# Sony_keyboard.net
KiCad netlist of a schematic drawn in EAGLE
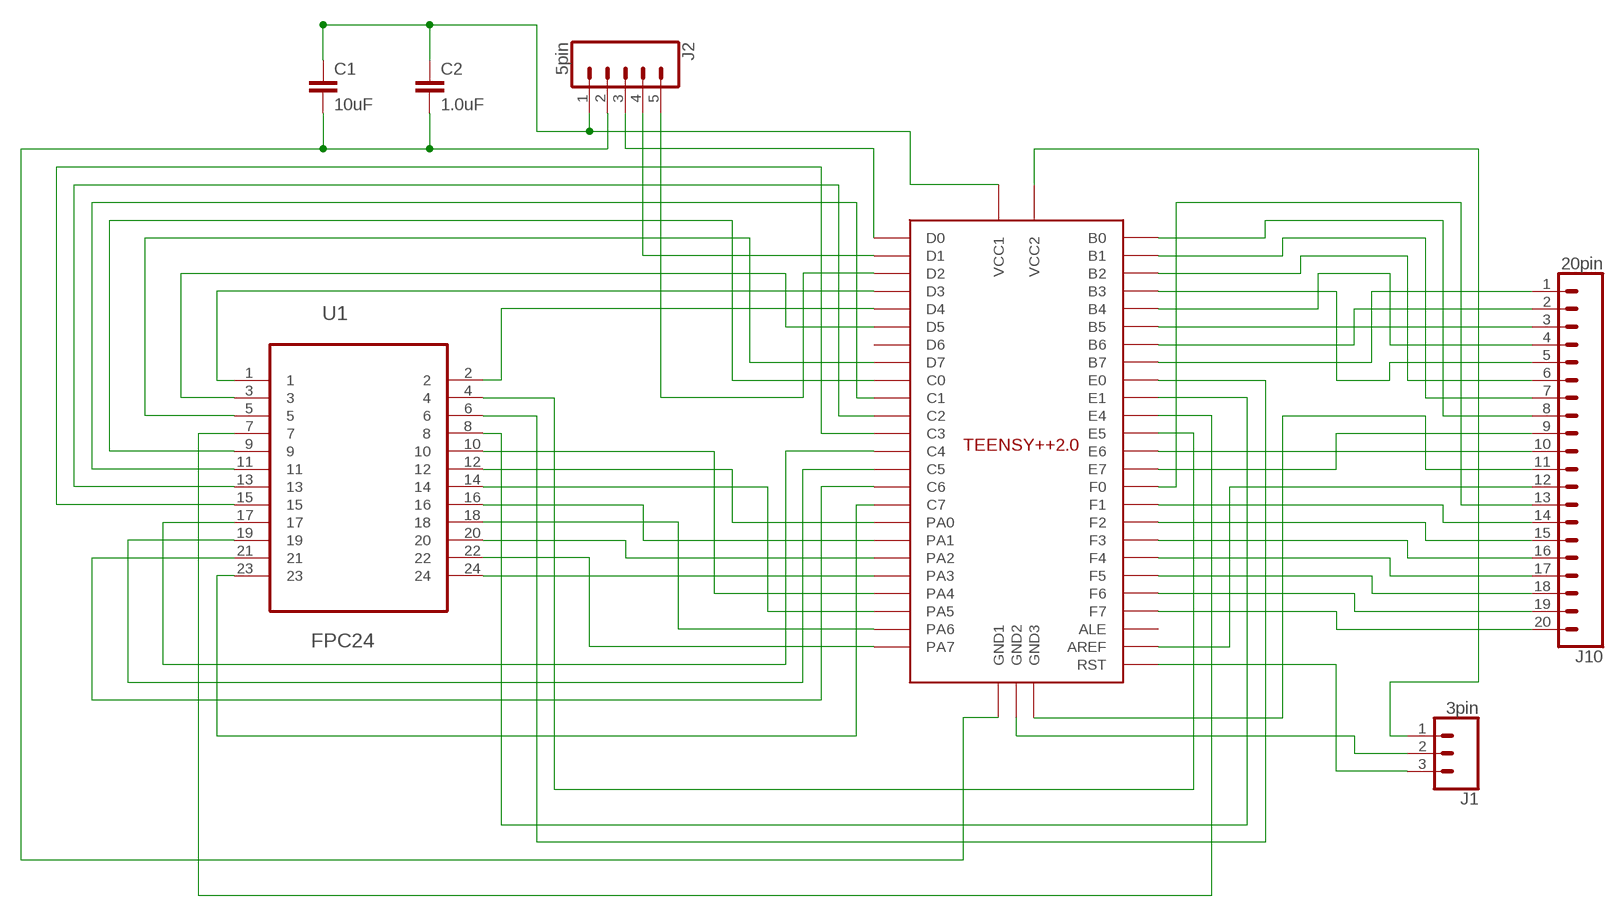
[diagram p0: schematic, sheet 1]

(export (version "E")
  (design (tool "Eeschema 10.0.6"))
  (components
    (comp (ref "C1")
      (value "10uF")
      (footprint "eagle-import:0603")
      (libsource (lib "eagle-import") (part "10UF-0603-6.3V-20%"))
    )
    (comp (ref "C2")
      (value "1.0uF")
      (footprint "eagle-import:0603")
      (libsource (lib "eagle-import") (part "1.0UF-0603-16V-10%"))
    )
    (comp (ref "J1")
      (value "3pin")
      (footprint "eagle-import:1X03")
      (libsource (lib "eagle-import") (part "CONN_03"))
    )
    (comp (ref "J2")
      (value "5pin")
      (footprint "eagle-import:1X05")
      (libsource (lib "eagle-import") (part "CONN_05"))
    )
    (comp (ref "J10")
      (value "20pin")
      (footprint "eagle-import:1X20")
      (libsource (lib "eagle-import") (part "CONN_20"))
    )
    (comp (ref "U1")
      (value "FPC24")
      (footprint "eagle-import:FPC24")
      (libsource (lib "eagle-import") (part "FPC24"))
    )
    (comp (ref "U2")
      (value "Teensy++2.0")
      (footprint "eagle-import:TEENSYPP2.0")
      (libsource (lib "eagle-import") (part "TEENSYPP2.0"))
    )
  )
  (nets
    (net (code "1") (name "Net-(C1-Pad1)") (class "Default")
      (node (ref "C1") (pin "1") (pinfunction "1_1") (pintype "passive"))
      (node (ref "C2") (pin "1") (pinfunction "1_1") (pintype "passive"))
      (node (ref "J2") (pin "1") (pinfunction "1_1") (pintype "passive"))
      (node (ref "U2") (pin "VCC1") (pinfunction "VCC1_VCC1") (pintype "bidirectional"))
    )
    (net (code "2") (name "Net-(C1-Pad2)") (class "Default")
      (node (ref "C1") (pin "2") (pinfunction "2_2") (pintype "passive"))
      (node (ref "C2") (pin "2") (pinfunction "2_2") (pintype "passive"))
      (node (ref "J2") (pin "2") (pinfunction "2_2") (pintype "passive"))
      (node (ref "U2") (pin "GND1") (pinfunction "GND1_GND1") (pintype "bidirectional"))
    )
    (net (code "3") (name "Net-(J1-Pad1)") (class "Default")
      (node (ref "J1") (pin "1") (pinfunction "1_1") (pintype "passive"))
      (node (ref "U2") (pin "VCC2") (pinfunction "VCC2_VCC2") (pintype "bidirectional"))
    )
    (net (code "4") (name "Net-(J1-Pad2)") (class "Default")
      (node (ref "J1") (pin "2") (pinfunction "2_2") (pintype "passive"))
      (node (ref "U2") (pin "GND2") (pinfunction "GND2_GND2") (pintype "bidirectional"))
    )
    (net (code "5") (name "Net-(J1-Pad3)") (class "Default")
      (node (ref "J1") (pin "3") (pinfunction "3_3") (pintype "passive"))
      (node (ref "U2") (pin "RST") (pinfunction "RST_RST") (pintype "bidirectional"))
    )
    (net (code "6") (name "Net-(J2-Pad3)") (class "Default")
      (node (ref "J2") (pin "3") (pinfunction "3_3") (pintype "passive"))
      (node (ref "U2") (pin "D0") (pinfunction "D0_D0") (pintype "bidirectional"))
    )
    (net (code "7") (name "Net-(J2-Pad4)") (class "Default")
      (node (ref "J2") (pin "4") (pinfunction "4_4") (pintype "passive"))
      (node (ref "U2") (pin "D1") (pinfunction "D1_D1") (pintype "bidirectional"))
    )
    (net (code "8") (name "Net-(J2-Pad5)") (class "Default")
      (node (ref "J2") (pin "5") (pinfunction "5_5") (pintype "passive"))
      (node (ref "U2") (pin "D2") (pinfunction "D2_D2") (pintype "bidirectional"))
    )
    (net (code "9") (name "Net-(J10-Pad1)") (class "Default")
      (node (ref "J10") (pin "1") (pinfunction "1_1") (pintype "passive"))
      (node (ref "U2") (pin "B7") (pinfunction "B7_B7") (pintype "bidirectional"))
    )
    (net (code "10") (name "Net-(J10-Pad2)") (class "Default")
      (node (ref "J10") (pin "2") (pinfunction "2_2") (pintype "passive"))
      (node (ref "U2") (pin "B6") (pinfunction "B6_B6") (pintype "bidirectional"))
    )
    (net (code "11") (name "Net-(J10-Pad3)") (class "Default")
      (node (ref "J10") (pin "3") (pinfunction "3_3") (pintype "passive"))
      (node (ref "U2") (pin "B5") (pinfunction "B5_B5") (pintype "bidirectional"))
    )
    (net (code "12") (name "Net-(J10-Pad4)") (class "Default")
      (node (ref "J10") (pin "4") (pinfunction "4_4") (pintype "passive"))
      (node (ref "U2") (pin "B4") (pinfunction "B4_B4") (pintype "bidirectional"))
    )
    (net (code "13") (name "Net-(J10-Pad5)") (class "Default")
      (node (ref "J10") (pin "5") (pinfunction "5_5") (pintype "passive"))
      (node (ref "U2") (pin "B3") (pinfunction "B3_B3") (pintype "bidirectional"))
    )
    (net (code "14") (name "Net-(J10-Pad6)") (class "Default")
      (node (ref "J10") (pin "6") (pinfunction "6_6") (pintype "passive"))
      (node (ref "U2") (pin "B2") (pinfunction "B2_B2") (pintype "bidirectional"))
    )
    (net (code "15") (name "Net-(J10-Pad7)") (class "Default")
      (node (ref "J10") (pin "7") (pinfunction "7_7") (pintype "passive"))
      (node (ref "U2") (pin "B1") (pinfunction "B1_B1") (pintype "bidirectional"))
    )
    (net (code "16") (name "Net-(J10-Pad8)") (class "Default")
      (node (ref "J10") (pin "8") (pinfunction "8_8") (pintype "passive"))
      (node (ref "U2") (pin "B0") (pinfunction "B0_B0") (pintype "bidirectional"))
    )
    (net (code "17") (name "Net-(J10-Pad9)") (class "Default")
      (node (ref "J10") (pin "9") (pinfunction "9_9") (pintype "passive"))
      (node (ref "U2") (pin "E7") (pinfunction "E7_E7") (pintype "bidirectional"))
    )
    (net (code "18") (name "Net-(J10-Pad10)") (class "Default")
      (node (ref "J10") (pin "10") (pinfunction "10_10") (pintype "passive"))
      (node (ref "U2") (pin "E6") (pinfunction "E6_E6") (pintype "bidirectional"))
    )
    (net (code "19") (name "Net-(J10-Pad11)") (class "Default")
      (node (ref "J10") (pin "11") (pinfunction "11_11") (pintype "passive"))
      (node (ref "U2") (pin "GND3") (pinfunction "GND3_GND3") (pintype "bidirectional"))
    )
    (net (code "20") (name "Net-(J10-Pad12)") (class "Default")
      (node (ref "J10") (pin "12") (pinfunction "12_12") (pintype "passive"))
      (node (ref "U2") (pin "AREF") (pinfunction "AREF_AREF") (pintype "bidirectional"))
    )
    (net (code "21") (name "Net-(J10-Pad13)") (class "Default")
      (node (ref "J10") (pin "13") (pinfunction "13_13") (pintype "passive"))
      (node (ref "U2") (pin "F0") (pinfunction "F0_F0") (pintype "bidirectional"))
    )
    (net (code "22") (name "Net-(J10-Pad14)") (class "Default")
      (node (ref "J10") (pin "14") (pinfunction "14_14") (pintype "passive"))
      (node (ref "U2") (pin "F1") (pinfunction "F1_F1") (pintype "bidirectional"))
    )
    (net (code "23") (name "Net-(J10-Pad15)") (class "Default")
      (node (ref "J10") (pin "15") (pinfunction "15_15") (pintype "passive"))
      (node (ref "U2") (pin "F2") (pinfunction "F2_F2") (pintype "bidirectional"))
    )
    (net (code "24") (name "Net-(J10-Pad16)") (class "Default")
      (node (ref "J10") (pin "16") (pinfunction "16_16") (pintype "passive"))
      (node (ref "U2") (pin "F3") (pinfunction "F3_F3") (pintype "bidirectional"))
    )
    (net (code "25") (name "Net-(J10-Pad17)") (class "Default")
      (node (ref "J10") (pin "17") (pinfunction "17_17") (pintype "passive"))
      (node (ref "U2") (pin "F4") (pinfunction "F4_F4") (pintype "bidirectional"))
    )
    (net (code "26") (name "Net-(J10-Pad18)") (class "Default")
      (node (ref "J10") (pin "18") (pinfunction "18_18") (pintype "passive"))
      (node (ref "U2") (pin "F5") (pinfunction "F5_F5") (pintype "bidirectional"))
    )
    (net (code "27") (name "Net-(J10-Pad19)") (class "Default")
      (node (ref "J10") (pin "19") (pinfunction "19_19") (pintype "passive"))
      (node (ref "U2") (pin "F6") (pinfunction "F6_F6") (pintype "bidirectional"))
    )
    (net (code "28") (name "Net-(J10-Pad20)") (class "Default")
      (node (ref "J10") (pin "20") (pinfunction "20_20") (pintype "passive"))
      (node (ref "U2") (pin "F7") (pinfunction "F7_F7") (pintype "bidirectional"))
    )
    (net (code "29") (name "Net-(U1-Pad1)") (class "Default")
      (node (ref "U1") (pin "1") (pinfunction "1_1") (pintype "passive"))
      (node (ref "U2") (pin "D3") (pinfunction "D3_D3") (pintype "bidirectional"))
    )
    (net (code "30") (name "Net-(U1-Pad2)") (class "Default")
      (node (ref "U1") (pin "2") (pinfunction "2_2") (pintype "passive"))
      (node (ref "U2") (pin "D4") (pinfunction "D4_D4") (pintype "bidirectional"))
    )
    (net (code "31") (name "Net-(U1-Pad3)") (class "Default")
      (node (ref "U1") (pin "3") (pinfunction "3_3") (pintype "passive"))
      (node (ref "U2") (pin "D5") (pinfunction "D5_D5") (pintype "bidirectional"))
    )
    (net (code "32") (name "Net-(U1-Pad4)") (class "Default")
      (node (ref "U1") (pin "4") (pinfunction "4_4") (pintype "passive"))
      (node (ref "U2") (pin "E5") (pinfunction "E5_E5") (pintype "bidirectional"))
    )
    (net (code "33") (name "Net-(U1-Pad5)") (class "Default")
      (node (ref "U1") (pin "5") (pinfunction "5_5") (pintype "passive"))
      (node (ref "U2") (pin "D7") (pinfunction "D7_D7") (pintype "bidirectional"))
    )
    (net (code "34") (name "Net-(U1-Pad6)") (class "Default")
      (node (ref "U1") (pin "6") (pinfunction "6_6") (pintype "passive"))
      (node (ref "U2") (pin "E0") (pinfunction "E0_E0") (pintype "bidirectional"))
    )
    (net (code "35") (name "Net-(U1-Pad7)") (class "Default")
      (node (ref "U1") (pin "7") (pinfunction "7_7") (pintype "passive"))
      (node (ref "U2") (pin "E4") (pinfunction "E4_E4") (pintype "bidirectional"))
    )
    (net (code "36") (name "Net-(U1-Pad8)") (class "Default")
      (node (ref "U1") (pin "8") (pinfunction "8_8") (pintype "passive"))
      (node (ref "U2") (pin "E1") (pinfunction "E1_E1") (pintype "bidirectional"))
    )
    (net (code "37") (name "Net-(U1-Pad9)") (class "Default")
      (node (ref "U1") (pin "9") (pinfunction "9_9") (pintype "passive"))
      (node (ref "U2") (pin "C0") (pinfunction "C0_C0") (pintype "bidirectional"))
    )
    (net (code "38") (name "Net-(U1-Pad10)") (class "Default")
      (node (ref "U1") (pin "10") (pinfunction "10_10") (pintype "passive"))
      (node (ref "U2") (pin "PA4") (pinfunction "PA4_PA4") (pintype "bidirectional"))
    )
    (net (code "39") (name "Net-(U1-Pad11)") (class "Default")
      (node (ref "U1") (pin "11") (pinfunction "11_11") (pintype "passive"))
      (node (ref "U2") (pin "C1") (pinfunction "C1_C1") (pintype "bidirectional"))
    )
    (net (code "40") (name "Net-(U1-Pad12)") (class "Default")
      (node (ref "U1") (pin "12") (pinfunction "12_12") (pintype "passive"))
      (node (ref "U2") (pin "PA0") (pinfunction "PA0_PA0") (pintype "bidirectional"))
    )
    (net (code "41") (name "Net-(U1-Pad13)") (class "Default")
      (node (ref "U1") (pin "13") (pinfunction "13_13") (pintype "passive"))
      (node (ref "U2") (pin "C2") (pinfunction "C2_C2") (pintype "bidirectional"))
    )
    (net (code "42") (name "Net-(U1-Pad14)") (class "Default")
      (node (ref "U1") (pin "14") (pinfunction "14_14") (pintype "passive"))
      (node (ref "U2") (pin "PA5") (pinfunction "PA5_PA5") (pintype "bidirectional"))
    )
    (net (code "43") (name "Net-(U1-Pad15)") (class "Default")
      (node (ref "U1") (pin "15") (pinfunction "15_15") (pintype "passive"))
      (node (ref "U2") (pin "C3") (pinfunction "C3_C3") (pintype "bidirectional"))
    )
    (net (code "44") (name "Net-(U1-Pad16)") (class "Default")
      (node (ref "U1") (pin "16") (pinfunction "16_16") (pintype "passive"))
      (node (ref "U2") (pin "PA1") (pinfunction "PA1_PA1") (pintype "bidirectional"))
    )
    (net (code "45") (name "Net-(U1-Pad17)") (class "Default")
      (node (ref "U1") (pin "17") (pinfunction "17_17") (pintype "passive"))
      (node (ref "U2") (pin "C4") (pinfunction "C4_C4") (pintype "bidirectional"))
    )
    (net (code "46") (name "Net-(U1-Pad18)") (class "Default")
      (node (ref "U1") (pin "18") (pinfunction "18_18") (pintype "passive"))
      (node (ref "U2") (pin "PA6") (pinfunction "PA6_PA6") (pintype "bidirectional"))
    )
    (net (code "47") (name "Net-(U1-Pad19)") (class "Default")
      (node (ref "U1") (pin "19") (pinfunction "19_19") (pintype "passive"))
      (node (ref "U2") (pin "C5") (pinfunction "C5_C5") (pintype "bidirectional"))
    )
    (net (code "48") (name "Net-(U1-Pad20)") (class "Default")
      (node (ref "U1") (pin "20") (pinfunction "20_20") (pintype "passive"))
      (node (ref "U2") (pin "PA2") (pinfunction "PA2_PA2") (pintype "bidirectional"))
    )
    (net (code "49") (name "Net-(U1-Pad21)") (class "Default")
      (node (ref "U1") (pin "21") (pinfunction "21_21") (pintype "passive"))
      (node (ref "U2") (pin "C6") (pinfunction "C6_C6") (pintype "bidirectional"))
    )
    (net (code "50") (name "Net-(U1-Pad22)") (class "Default")
      (node (ref "U1") (pin "22") (pinfunction "22_22") (pintype "passive"))
      (node (ref "U2") (pin "PA7") (pinfunction "PA7_PA7") (pintype "bidirectional"))
    )
    (net (code "51") (name "Net-(U1-Pad23)") (class "Default")
      (node (ref "U1") (pin "23") (pinfunction "23_23") (pintype "passive"))
      (node (ref "U2") (pin "C7") (pinfunction "C7_C7") (pintype "bidirectional"))
    )
    (net (code "52") (name "Net-(U1-Pad24)") (class "Default")
      (node (ref "U1") (pin "24") (pinfunction "24_24") (pintype "passive"))
      (node (ref "U2") (pin "PA3") (pinfunction "PA3_PA3") (pintype "bidirectional"))
    )
    (net (code "53") (name "unconnected-(U2-PadALE)") (class "Default")
      (node (ref "U2") (pin "ALE") (pinfunction "ALE_ALE") (pintype "bidirectional"))
    )
    (net (code "54") (name "unconnected-(U2-PadD6)") (class "Default")
      (node (ref "U2") (pin "D6") (pinfunction "D6_D6") (pintype "bidirectional"))
    )
  )
)
